# Filter_Pi.net
KiCad netlist of a schematic drawn in Altium Designer
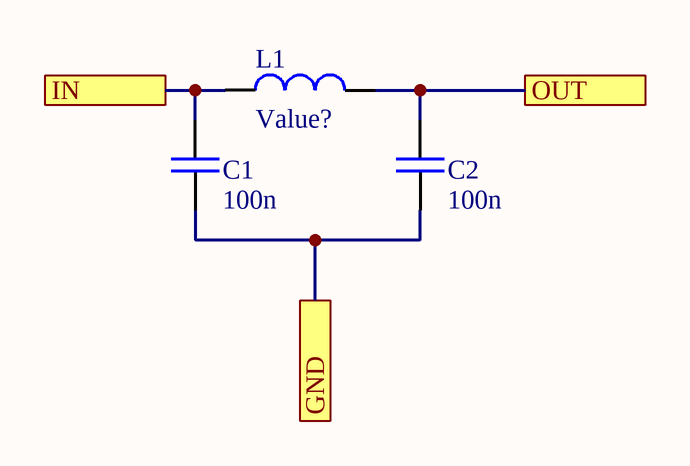
[diagram p0: Filter_Pi.SchDoc]

(export (version "E")
  (design (tool "Eeschema 10.0.6"))
  (components
    (comp (ref "C1")
      (value "100n")
      (footprint "CAP 0805/2012")
      (description "Bipolar ceramic capacitor SMD")
      (fields (field (name "VALIDATION") "Valid"))
      (libsource (lib "aKaReZa") (part "Cap_Multi_SMD_100nF_0805"))
    )
    (comp (ref "C2")
      (value "100n")
      (footprint "CAP 0805/2012")
      (description "Bipolar ceramic capacitor SMD")
      (fields (field (name "VALIDATION") "Valid"))
      (libsource (lib "aKaReZa") (part "Cap_Multi_SMD_100nF_0805"))
    )
    (comp (ref "L1")
      (value "Value?")
      (footprint "IND0805")
      (description "Inductor")
      (fields (field (name "VALIDATION") "Valid"))
      (libsource (lib "aKaReZa") (part "Ind_SMD_0805"))
    )
  )
  (nets
    (net (code "1") (name "/GND") (class "Default")
      (node (ref "C1") (pin "2") (pinfunction "2_2") (pintype "passive"))
      (node (ref "C2") (pin "2") (pinfunction "2_2") (pintype "passive"))
    )
    (net (code "2") (name "/IN") (class "Default")
      (node (ref "C1") (pin "1") (pinfunction "1_1") (pintype "passive"))
      (node (ref "L1") (pin "1") (pinfunction "1_1") (pintype "passive"))
    )
    (net (code "3") (name "/OUT") (class "Default")
      (node (ref "C2") (pin "1") (pinfunction "1_1") (pintype "passive"))
      (node (ref "L1") (pin "2") (pinfunction "2_2") (pintype "passive"))
    )
  )
)
